# buzzer.net
KiCad netlist of a schematic drawn in Altium Designer
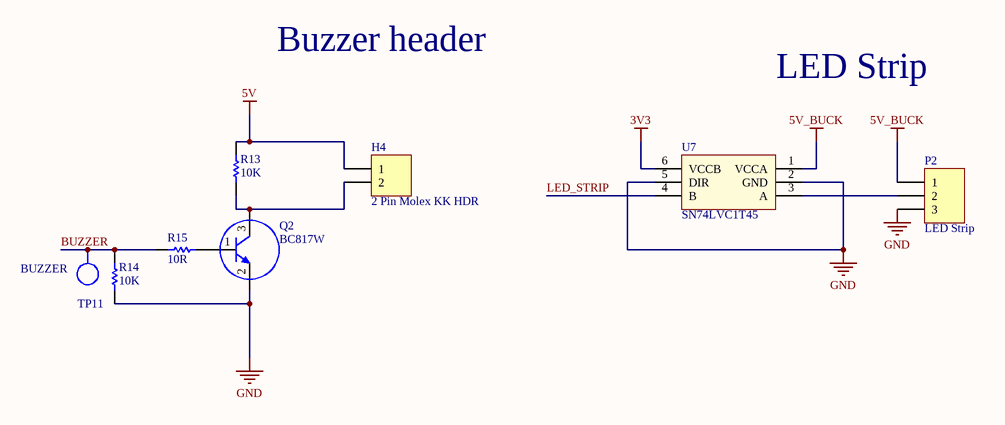
[diagram p0: buzzer.SchDoc]

(export (version "E")
  (design (tool "Eeschema 10.0.6"))
  (components
    (comp (ref "H4")
      (value "2 Pin Molex KK HDR")
      (footprint "MOLEX_KK_2_HDR")
      (description "CONN HEADER 2POS 2.54mm VERT_Thru Hole")
      (libsource (lib "ECE AD19Components_19V1") (part "JA_MOLEX_KK_2POS"))
    )
    (comp (ref "P2")
      (value "LED Strip")
      (footprint "MHDR1X3")
      (description "Header, 3-Pin")
      (fields (field (name "PUBLISHER") "Altium Limited"))
      (libsource (lib "Miscellaneous Connectors") (part "MHDR1X3"))
    )
    (comp (ref "Q2")
      (value "BC817W")
      (footprint "SOT323_M")
      (description "NPN GP Bipolar Transistor 45V 500mA SOT323")
      (fields (field (name "MANUFACTURER") "NXP"))
      (libsource (lib "ECE AD19Components_19V1") (part "TB_BC817W"))
    )
    (comp (ref "R13")
      (value "10K")
      (footprint "RESC1608L")
      (description "RES 10.0K OHM 1/10W 5% 0603 SMD")
      (libsource (lib "ECE AD19Components_19V1") (part "RS_10K"))
    )
    (comp (ref "R14")
      (value "10K")
      (footprint "RESC1608L")
      (description "RES 10.0K OHM 1/10W 5% 0603 SMD")
      (libsource (lib "ECE AD19Components_19V1") (part "RS_10K"))
    )
    (comp (ref "R15")
      (value "10R")
      (footprint "RESC1608L")
      (description "RES 10 OHM 1/10W 5% 0603 SMD")
      (libsource (lib "ECE AD19Components_19V1") (part "RS_10R"))
    )
    (comp (ref "TP11")
      (value "BUZZER")
      (footprint "TP_1206")
      (description "Test-Point 3.3x1.6x2.1mm SMD")
      (fields
        (field (name "MANUFACTURER") "Harwin Inc")
        (field (name "MANUFACTURER PART NUMBER") "S1751-46R")
      )
      (libsource (lib "ECE AD19Components_19V1") (part "TP_1206"))
    )
    (comp (ref "U7")
      (value "SN74LVC1T45")
      (footprint "SOT23-6_N")
      (description "1.8V - 5V level converter")
      (libsource (lib "ENCE461_extras_2020") (part "SN74LVC1T45"))
    )
  )
  (nets
    (net (code "1") (name "/BUZZER") (class "Default")
      (node (ref "R14") (pin "2") (pinfunction "2_2") (pintype "passive"))
      (node (ref "R15") (pin "1") (pinfunction "1_1") (pintype "passive"))
      (node (ref "TP11") (pin "1") (pinfunction "1_1") (pintype "passive"))
    )
    (net (code "2") (name "/LED_STRIP") (class "Default")
      (node (ref "U7") (pin "4") (pinfunction "B_4") (pintype "passive"))
    )
    (net (code "3") (name "3V3") (class "Default")
      (node (ref "U7") (pin "6") (pinfunction "VCCB_6") (pintype "passive"))
    )
    (net (code "4") (name "5V") (class "Default")
      (node (ref "H4") (pin "1") (pinfunction "1_1") (pintype "passive"))
      (node (ref "R13") (pin "2") (pinfunction "2_2") (pintype "passive"))
    )
    (net (code "5") (name "5V_BUCK") (class "Default")
      (node (ref "P2") (pin "1") (pinfunction "1_1") (pintype "passive"))
      (node (ref "U7") (pin "1") (pinfunction "VCCA_1") (pintype "passive"))
    )
    (net (code "6") (name "GND") (class "Default")
      (node (ref "P2") (pin "3") (pinfunction "3_3") (pintype "passive"))
      (node (ref "Q2") (pin "2") (pinfunction "2_2") (pintype "passive"))
      (node (ref "R14") (pin "1") (pinfunction "1_1") (pintype "passive"))
      (node (ref "U7") (pin "2") (pinfunction "GND_2") (pintype "passive"))
      (node (ref "U7") (pin "5") (pinfunction "DIR_5") (pintype "passive"))
    )
    (net (code "7") (name "Net-(H4-Pad2)") (class "Default")
      (node (ref "H4") (pin "2") (pinfunction "2_2") (pintype "passive"))
      (node (ref "Q2") (pin "3") (pinfunction "3_3") (pintype "passive"))
      (node (ref "R13") (pin "1") (pinfunction "1_1") (pintype "passive"))
    )
    (net (code "8") (name "Net-(Q2-Pad1)") (class "Default")
      (node (ref "Q2") (pin "1") (pinfunction "1_1") (pintype "passive"))
      (node (ref "R15") (pin "2") (pinfunction "2_2") (pintype "passive"))
    )
    (net (code "9") (name "Net-(U7-A)") (class "Default")
      (node (ref "P2") (pin "2") (pinfunction "2_2") (pintype "passive"))
      (node (ref "U7") (pin "3") (pinfunction "A_3") (pintype "passive"))
    )
  )
)
